# Voltmeter_PCB_RTC_ESP_v3.net
KiCad netlist of a schematic drawn in EAGLE
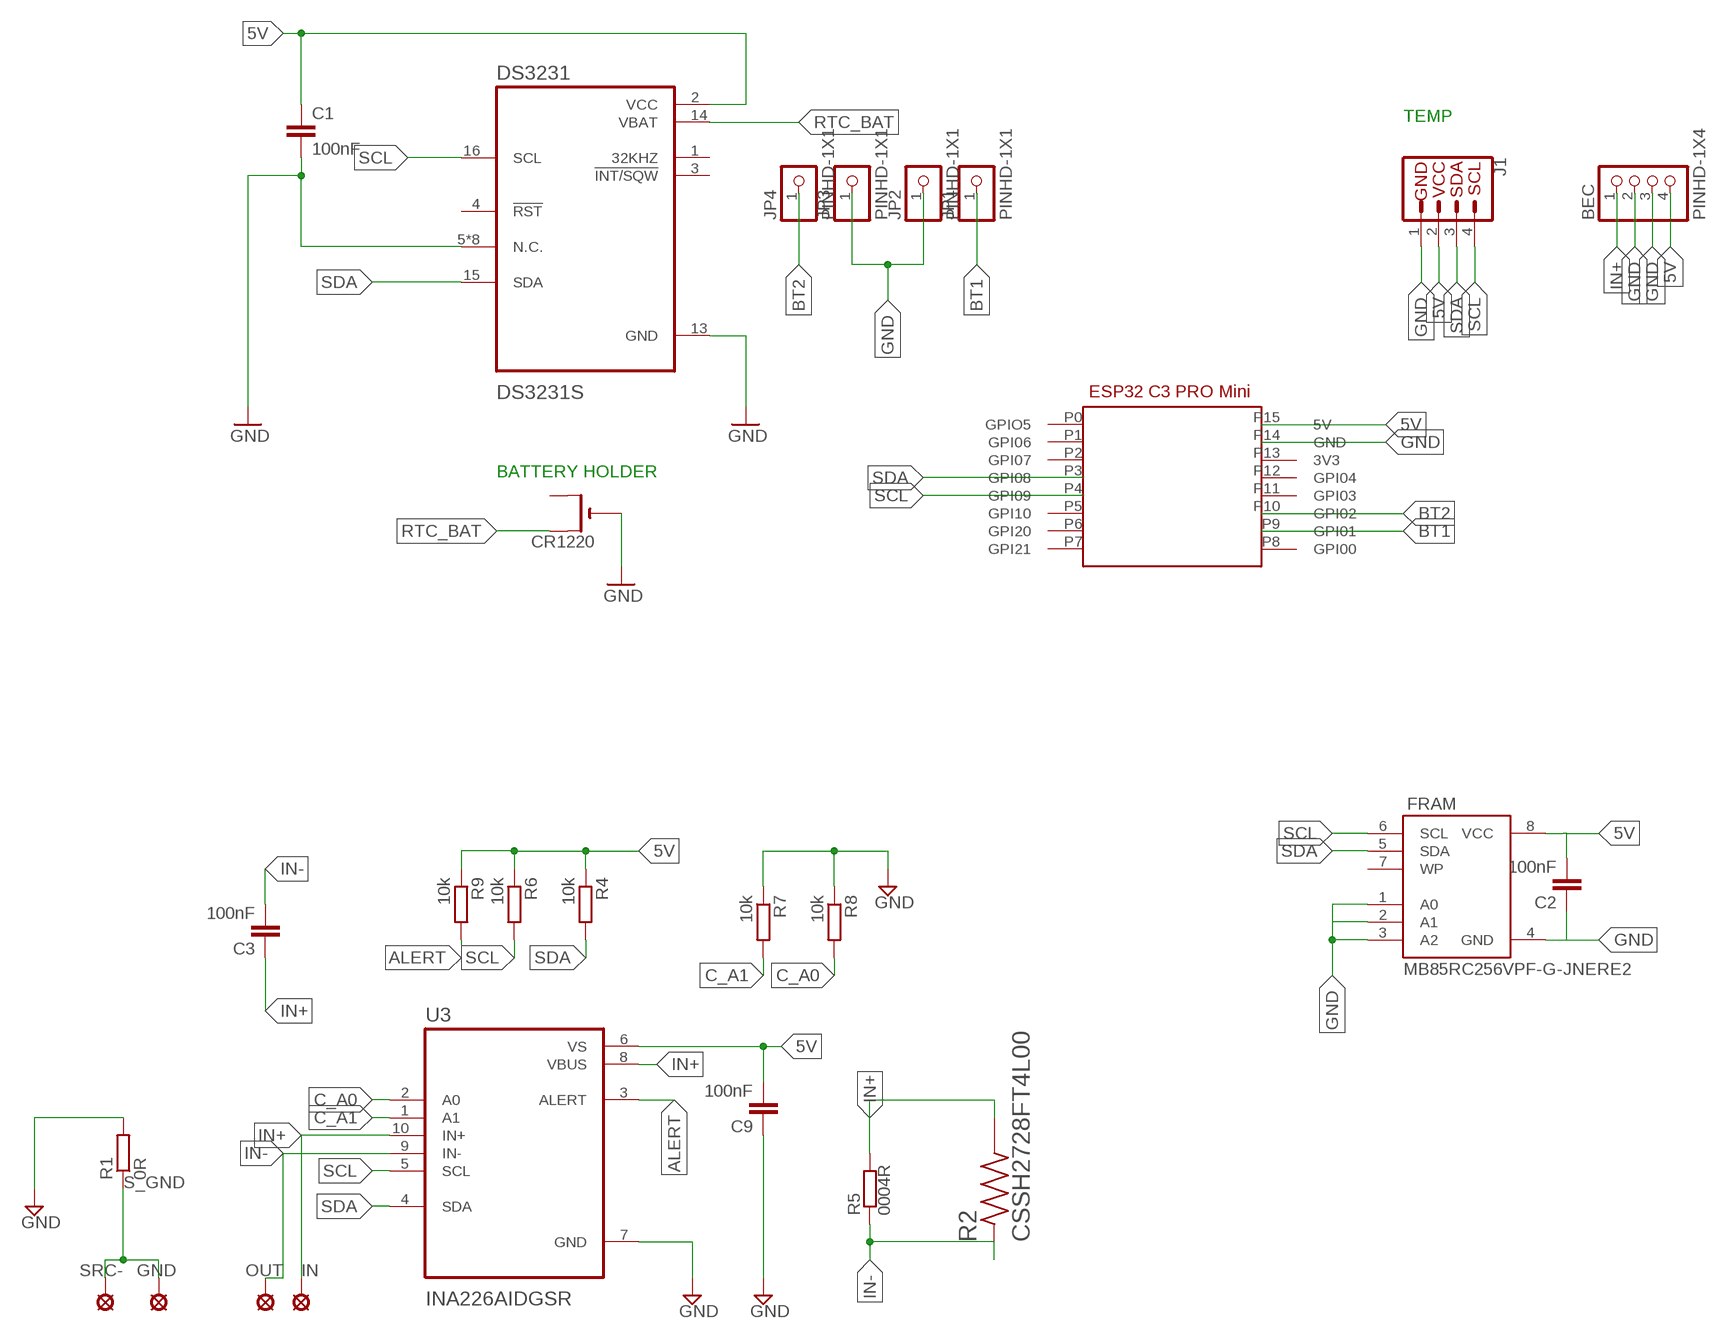
[diagram p0: schematic, sheet 1]

(export (version "E")
  (design (tool "Eeschema 10.0.6"))
  (components
    (comp (ref "BEC")
      (value "PINHD-1X4")
      (footprint "eagle-import:1X04")
      (libsource (lib "eagle-import") (part "PINHD-1X4"))
    )
    (comp (ref "C1")
      (value "100nF")
      (footprint "eagle-import:C0603")
      (libsource (lib "eagle-import") (part "resistor_348_C-EUC0603"))
    )
    (comp (ref "C2")
      (value "100nF")
      (footprint "eagle-import:C0603")
      (libsource (lib "eagle-import") (part "C-EUC0603"))
    )
    (comp (ref "C3")
      (value "100nF")
      (footprint "eagle-import:C0603")
      (libsource (lib "eagle-import") (part "C-EUC0603"))
    )
    (comp (ref "C9")
      (value "100nF")
      (footprint "eagle-import:C0603")
      (libsource (lib "eagle-import") (part "C-EUC0603"))
    )
    (comp (ref "CR1220")
      (value "CR1220SMT")
      (footprint "eagle-import:CR1220-SMD")
      (libsource (lib "eagle-import") (part "CR1220SMT"))
    )
    (comp (ref "DS3231")
      (value "DS3231S")
      (footprint "eagle-import:SOIC127P1032X265-16N")
      (fields (field (name "MF") "Maxim Integrated"))
      (libsource (lib "eagle-import") (part "DS3231S"))
    )
    (comp (ref "FRAM")
      (value "MB85RC256VPF-G-JNERE2")
      (footprint "eagle-import:SOIC8_208MIL")
      (fields (field (name "MF") "Fujitsu Semiconductors") (field (name "MP") "MB85RC256VPFGJNERE2"))
      (libsource (lib "eagle-import") (part "MB85RC256VPF-G-JNERE2"))
    )
    (comp (ref "GND")
      (value "SE14")
      (footprint "eagle-import:SE14")
      (libsource (lib "eagle-import") (part "SE14"))
    )
    (comp (ref "IN")
      (value "SE14")
      (footprint "eagle-import:SE14")
      (libsource (lib "eagle-import") (part "SE14"))
    )
    (comp (ref "J1")
      (value "QWIIC_CONNECTORJS-1MM")
      (footprint "eagle-import:1X04_1MM_RA")
      (libsource (lib "eagle-import") (part "QWIIC_CONNECTORJS-1MM"))
    )
    (comp (ref "JP1")
      (value "PINHD-1X1")
      (footprint "eagle-import:1X01")
      (libsource (lib "eagle-import") (part "PINHD-1X1"))
    )
    (comp (ref "JP2")
      (value "PINHD-1X1")
      (footprint "eagle-import:1X01")
      (libsource (lib "eagle-import") (part "PINHD-1X1"))
    )
    (comp (ref "JP3")
      (value "PINHD-1X1")
      (footprint "eagle-import:1X01")
      (libsource (lib "eagle-import") (part "PINHD-1X1"))
    )
    (comp (ref "JP4")
      (value "PINHD-1X1")
      (footprint "eagle-import:1X01")
      (libsource (lib "eagle-import") (part "PINHD-1X1"))
    )
    (comp (ref "OUT")
      (value "SE14")
      (footprint "eagle-import:SE14")
      (libsource (lib "eagle-import") (part "SE14"))
    )
    (comp (ref "R1")
      (value "0R")
      (footprint "eagle-import:R1206")
      (libsource (lib "eagle-import") (part "R-EU_R1206"))
    )
    (comp (ref "R2")
      (value "CSSH2728FT4L00")
      (footprint "eagle-import:RESC6771X124N")
      (fields (field (name "MF") "Stackpole Electronics Inc"))
      (libsource (lib "eagle-import") (part "CSSH2728FT4L00"))
    )
    (comp (ref "R4")
      (value "10k")
      (footprint "eagle-import:R0603")
      (libsource (lib "eagle-import") (part "R-EU_R0603"))
    )
    (comp (ref "R5")
      (value "0004R")
      (footprint "eagle-import:BVS")
      (libsource (lib "eagle-import") (part "BVS"))
    )
    (comp (ref "R6")
      (value "10k")
      (footprint "eagle-import:R0603")
      (libsource (lib "eagle-import") (part "R-EU_R0603"))
    )
    (comp (ref "R7")
      (value "10k")
      (footprint "eagle-import:R0603")
      (libsource (lib "eagle-import") (part "R-EU_R0603"))
    )
    (comp (ref "R8")
      (value "10k")
      (footprint "eagle-import:R0603")
      (libsource (lib "eagle-import") (part "R-EU_R0603"))
    )
    (comp (ref "R9")
      (value "10k")
      (footprint "eagle-import:R0603")
      (libsource (lib "eagle-import") (part "R-EU_R0603"))
    )
    (comp (ref "SRC-")
      (value "SE14")
      (footprint "eagle-import:SE14")
      (libsource (lib "eagle-import") (part "SE14"))
    )
    (comp (ref "U$1")
      (value "ESP32_C3_PROV1")
      (footprint "eagle-import:ESP32_C2_PRO")
      (libsource (lib "eagle-import") (part "ESP32_C3_PROV1"))
    )
    (comp (ref "U3")
      (value "INA226AIDGSR")
      (footprint "eagle-import:SOP50P490X110-10N")
      (fields (field (name "MF") "Texas Instruments"))
      (libsource (lib "eagle-import") (part "INA226AIDGSR"))
    )
  )
  (nets
    (net (code "1") (name "/S_GND") (class "Default")
      (node (ref "GND") (pin "MP") (pinfunction "MP_MP") (pintype "passive"))
      (node (ref "R1") (pin "1") (pinfunction "1_1") (pintype "passive"))
      (node (ref "SRC-") (pin "MP") (pinfunction "MP_MP") (pintype "passive"))
    )
    (net (code "2") (name "5V") (class "Default")
      (node (ref "BEC") (pin "4") (pinfunction "4_4") (pintype "passive"))
      (node (ref "C1") (pin "1") (pinfunction "1_1") (pintype "passive"))
      (node (ref "C2") (pin "2") (pinfunction "2_2") (pintype "passive"))
      (node (ref "C9") (pin "2") (pinfunction "2_2") (pintype "passive"))
      (node (ref "DS3231") (pin "2") (pinfunction "VCC_2") (pintype "power_in"))
      (node (ref "FRAM") (pin "8") (pinfunction "VCC_8") (pintype "bidirectional"))
      (node (ref "J1") (pin "2") (pinfunction "VCC_2") (pintype "power_in"))
      (node (ref "R4") (pin "1") (pinfunction "1_1") (pintype "passive"))
      (node (ref "R6") (pin "1") (pinfunction "1_1") (pintype "passive"))
      (node (ref "R9") (pin "1") (pinfunction "1_1") (pintype "passive"))
      (node (ref "U$1") (pin "P15") (pinfunction "5V_P15") (pintype "bidirectional"))
      (node (ref "U3") (pin "6") (pinfunction "VS_6") (pintype "power_in"))
    )
    (net (code "3") (name "ALERT") (class "Default")
      (node (ref "R9") (pin "2") (pinfunction "2_2") (pintype "passive"))
      (node (ref "U3") (pin "3") (pinfunction "ALERT_3") (pintype "output"))
    )
    (net (code "4") (name "BT1") (class "Default")
      (node (ref "JP1") (pin "1") (pinfunction "1_1") (pintype "passive"))
      (node (ref "U$1") (pin "P9") (pinfunction "GPI01_P9") (pintype "bidirectional"))
    )
    (net (code "5") (name "BT2") (class "Default")
      (node (ref "JP4") (pin "1") (pinfunction "1_1") (pintype "passive"))
      (node (ref "U$1") (pin "P10") (pinfunction "GPI02_P10") (pintype "bidirectional"))
    )
    (net (code "6") (name "C_A0") (class "Default")
      (node (ref "R8") (pin "2") (pinfunction "2_2") (pintype "passive"))
      (node (ref "U3") (pin "2") (pinfunction "A0_2") (pintype "input"))
    )
    (net (code "7") (name "C_A1") (class "Default")
      (node (ref "R7") (pin "2") (pinfunction "2_2") (pintype "passive"))
      (node (ref "U3") (pin "1") (pinfunction "A1_1") (pintype "input"))
    )
    (net (code "8") (name "GND") (class "Default")
      (node (ref "BEC") (pin "2") (pinfunction "2_2") (pintype "passive"))
      (node (ref "BEC") (pin "3") (pinfunction "3_3") (pintype "passive"))
      (node (ref "C1") (pin "2") (pinfunction "2_2") (pintype "passive"))
      (node (ref "C2") (pin "1") (pinfunction "1_1") (pintype "passive"))
      (node (ref "C9") (pin "1") (pinfunction "1_1") (pintype "passive"))
      (node (ref "CR1220") (pin "-") (pinfunction "-_-") (pintype "passive"))
      (node (ref "DS3231") (pin "10") (pinfunction "N.C._10") (pintype "bidirectional"))
      (node (ref "DS3231") (pin "11") (pinfunction "N.C._11") (pintype "bidirectional"))
      (node (ref "DS3231") (pin "12") (pinfunction "N.C._12") (pintype "bidirectional"))
      (node (ref "DS3231") (pin "13") (pinfunction "GND_13") (pintype "power_in"))
      (node (ref "DS3231") (pin "5") (pinfunction "N.C._5") (pintype "bidirectional"))
      (node (ref "DS3231") (pin "6") (pinfunction "N.C._6") (pintype "bidirectional"))
      (node (ref "DS3231") (pin "7") (pinfunction "N.C._7") (pintype "bidirectional"))
      (node (ref "DS3231") (pin "8") (pinfunction "N.C._8") (pintype "bidirectional"))
      (node (ref "DS3231") (pin "9") (pinfunction "N.C._9") (pintype "bidirectional"))
      (node (ref "FRAM") (pin "1") (pinfunction "A0_1") (pintype "bidirectional"))
      (node (ref "FRAM") (pin "3") (pinfunction "A2_3") (pintype "bidirectional"))
      (node (ref "FRAM") (pin "4") (pinfunction "GND_4") (pintype "bidirectional"))
      (node (ref "J1") (pin "1") (pinfunction "GND_1") (pintype "power_in"))
      (node (ref "JP2") (pin "1") (pinfunction "1_1") (pintype "passive"))
      (node (ref "JP3") (pin "1") (pinfunction "1_1") (pintype "passive"))
      (node (ref "R1") (pin "2") (pinfunction "2_2") (pintype "passive"))
      (node (ref "R7") (pin "1") (pinfunction "1_1") (pintype "passive"))
      (node (ref "R8") (pin "1") (pinfunction "1_1") (pintype "passive"))
      (node (ref "U$1") (pin "P14") (pinfunction "GND_P14") (pintype "bidirectional"))
      (node (ref "U3") (pin "7") (pinfunction "GND_7") (pintype "power_in"))
    )
    (net (code "9") (name "IN+") (class "Default")
      (node (ref "BEC") (pin "1") (pinfunction "1_1") (pintype "passive"))
      (node (ref "C3") (pin "1") (pinfunction "1_1") (pintype "passive"))
      (node (ref "IN") (pin "MP") (pinfunction "MP_MP") (pintype "passive"))
      (node (ref "R2") (pin "2") (pinfunction "2_2") (pintype "passive"))
      (node (ref "R5") (pin "1") (pinfunction "1_1") (pintype "passive"))
      (node (ref "U3") (pin "10") (pinfunction "IN+_10") (pintype "input"))
      (node (ref "U3") (pin "8") (pinfunction "VBUS_8") (pintype "power_in"))
    )
    (net (code "10") (name "IN-") (class "Default")
      (node (ref "C3") (pin "2") (pinfunction "2_2") (pintype "passive"))
      (node (ref "OUT") (pin "MP") (pinfunction "MP_MP") (pintype "passive"))
      (node (ref "R2") (pin "1") (pinfunction "1_1") (pintype "passive"))
      (node (ref "R5") (pin "2") (pinfunction "2_2") (pintype "passive"))
      (node (ref "U3") (pin "9") (pinfunction "IN-_9") (pintype "input"))
    )
    (net (code "11") (name "RTC_BAT") (class "Default")
      (node (ref "CR1220") (pin "+$1") (pinfunction "+_+$1") (pintype "passive"))
      (node (ref "DS3231") (pin "14") (pinfunction "VBAT_14") (pintype "power_in"))
    )
    (net (code "12") (name "SCL") (class "Default")
      (node (ref "DS3231") (pin "16") (pinfunction "SCL_16") (pintype "input"))
      (node (ref "FRAM") (pin "6") (pinfunction "SCL_6") (pintype "bidirectional"))
      (node (ref "J1") (pin "4") (pinfunction "SCL_4") (pintype "passive"))
      (node (ref "R6") (pin "2") (pinfunction "2_2") (pintype "passive"))
      (node (ref "U$1") (pin "P4") (pinfunction "GPI09_P4") (pintype "bidirectional"))
      (node (ref "U3") (pin "5") (pinfunction "SCL_5") (pintype "input"))
    )
    (net (code "13") (name "SDA") (class "Default")
      (node (ref "DS3231") (pin "15") (pinfunction "SDA_15") (pintype "bidirectional"))
      (node (ref "FRAM") (pin "5") (pinfunction "SDA_5") (pintype "bidirectional"))
      (node (ref "J1") (pin "3") (pinfunction "SDA_3") (pintype "passive"))
      (node (ref "R4") (pin "2") (pinfunction "2_2") (pintype "passive"))
      (node (ref "U$1") (pin "P3") (pinfunction "GPI08_P3") (pintype "bidirectional"))
      (node (ref "U3") (pin "4") (pinfunction "SDA_4") (pintype "bidirectional"))
    )
    (net (code "14") (name "unconnected-(CR1220-+1-Pad+$2)") (class "Default")
      (node (ref "CR1220") (pin "+$2") (pinfunction "+1_+$2") (pintype "passive"))
    )
    (net (code "15") (name "unconnected-(DS3231-32KHZ-Pad1)") (class "Default")
      (node (ref "DS3231") (pin "1") (pinfunction "32KHZ_1") (pintype "output"))
    )
    (net (code "16") (name "unconnected-(DS3231-~{INT{slash}SQW}-Pad3)") (class "Default")
      (node (ref "DS3231") (pin "3") (pinfunction "~{INT/SQW}_3") (pintype "output"))
    )
    (net (code "17") (name "unconnected-(DS3231-~{RST}-Pad4)") (class "Default")
      (node (ref "DS3231") (pin "4") (pinfunction "~{RST}_4") (pintype "bidirectional"))
    )
    (net (code "18") (name "unconnected-(FRAM-A1-Pad2)") (class "Default")
      (node (ref "FRAM") (pin "2") (pinfunction "A1_2") (pintype "bidirectional"))
    )
    (net (code "19") (name "unconnected-(FRAM-WP-Pad7)") (class "Default")
      (node (ref "FRAM") (pin "7") (pinfunction "WP_7") (pintype "bidirectional"))
    )
    (net (code "20") (name "unconnected-(U$1-3V3-PadP13)") (class "Default")
      (node (ref "U$1") (pin "P13") (pinfunction "3V3_P13") (pintype "bidirectional"))
    )
    (net (code "21") (name "unconnected-(U$1-GPI00-PadP8)") (class "Default")
      (node (ref "U$1") (pin "P8") (pinfunction "GPI00_P8") (pintype "bidirectional"))
    )
    (net (code "22") (name "unconnected-(U$1-GPI03-PadP11)") (class "Default")
      (node (ref "U$1") (pin "P11") (pinfunction "GPI03_P11") (pintype "bidirectional"))
    )
    (net (code "23") (name "unconnected-(U$1-GPI04-PadP12)") (class "Default")
      (node (ref "U$1") (pin "P12") (pinfunction "GPI04_P12") (pintype "bidirectional"))
    )
    (net (code "24") (name "unconnected-(U$1-GPI06-PadP1)") (class "Default")
      (node (ref "U$1") (pin "P1") (pinfunction "GPI06_P1") (pintype "bidirectional"))
    )
    (net (code "25") (name "unconnected-(U$1-GPI07-PadP2)") (class "Default")
      (node (ref "U$1") (pin "P2") (pinfunction "GPI07_P2") (pintype "bidirectional"))
    )
    (net (code "26") (name "unconnected-(U$1-GPI10-PadP5)") (class "Default")
      (node (ref "U$1") (pin "P5") (pinfunction "GPI10_P5") (pintype "bidirectional"))
    )
    (net (code "27") (name "unconnected-(U$1-GPI20-PadP6)") (class "Default")
      (node (ref "U$1") (pin "P6") (pinfunction "GPI20_P6") (pintype "bidirectional"))
    )
    (net (code "28") (name "unconnected-(U$1-GPI21-PadP7)") (class "Default")
      (node (ref "U$1") (pin "P7") (pinfunction "GPI21_P7") (pintype "bidirectional"))
    )
    (net (code "29") (name "unconnected-(U$1-GPIO5-PadP0)") (class "Default")
      (node (ref "U$1") (pin "P0") (pinfunction "GPIO5_P0") (pintype "bidirectional"))
    )
  )
)
